# ms5839_without_trub.net
KiCad netlist of a schematic drawn in EAGLE
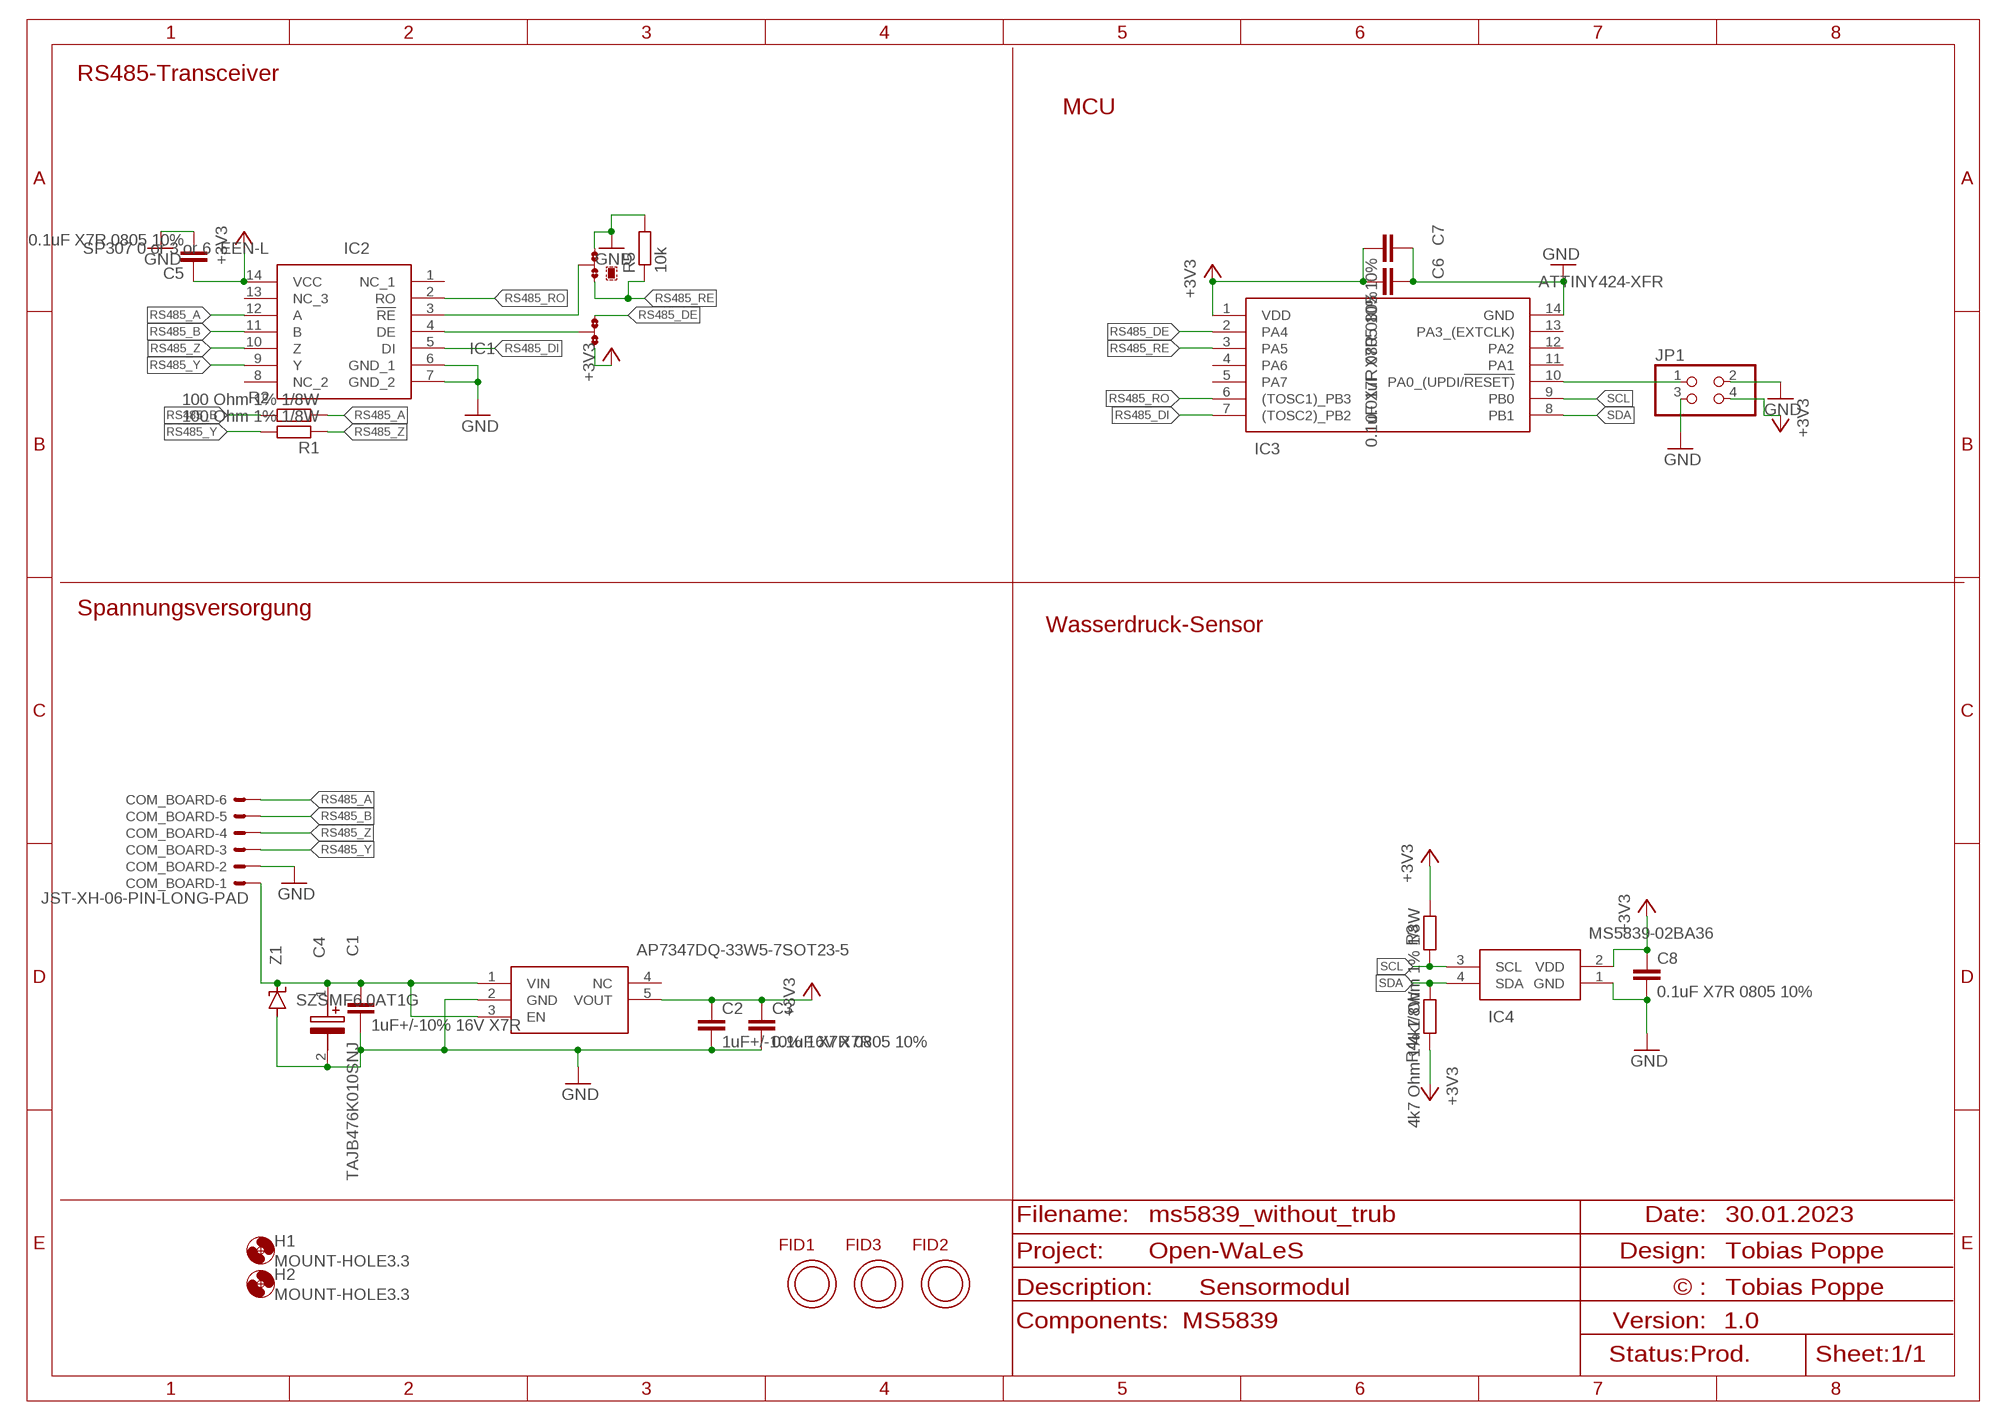
[diagram p0: schematic, sheet 1]

(export (version "E")
  (design (tool "Eeschema 10.0.6"))
  (components
    (comp (ref "C1")
      (value "1uF+/-10% 16V X7R")
      (footprint "eagle-import:C0805")
      (libsource (lib "eagle-import") (part "C-EUC0805"))
    )
    (comp (ref "C2")
      (value "1uF+/-10% 16V X7R")
      (footprint "eagle-import:C0805")
      (libsource (lib "eagle-import") (part "C-EUC0805"))
    )
    (comp (ref "C3")
      (value "0.1uF X7R 0805 10%")
      (footprint "eagle-import:C0805")
      (libsource (lib "eagle-import") (part "C-EUC0805"))
    )
    (comp (ref "C4")
      (value "TAJB476K010SNJ")
      (footprint "eagle-import:CAPPM3528X210N")
      (fields (field (name "MOUSER_PART_NUMBER") "581-TAJB476K010SNJ"))
      (libsource (lib "eagle-import") (part "TAJB476K010SNJ"))
    )
    (comp (ref "C5")
      (value "0.1uF X7R 0805 10%")
      (footprint "eagle-import:C0805")
      (libsource (lib "eagle-import") (part "C-EUC0805"))
    )
    (comp (ref "C6")
      (value "0.1uF X7R 0805 10%")
      (footprint "eagle-import:C0805")
      (libsource (lib "eagle-import") (part "C-EUC0805"))
    )
    (comp (ref "C7")
      (value "0.01uF X7R 0805 10%")
      (footprint "eagle-import:C0805")
      (libsource (lib "eagle-import") (part "C-EUC0805"))
    )
    (comp (ref "C8")
      (value "0.1uF X7R 0805 10%")
      (footprint "eagle-import:C0805")
      (libsource (lib "eagle-import") (part "C-EUC0805"))
    )
    (comp (ref "COM_BOARD")
      (value "JST-XH-06-PIN-LONG-PAD")
      (footprint "eagle-import:JST-XH-06-PACKAGE-LONG-PAD")
      (libsource (lib "eagle-import") (part "JST-XH-06-PIN-LONG-PAD"))
    )
    (comp (ref "FID1")
      (value "OPEN-PNP-FIDUCIAL")
      (footprint "eagle-import:OPEN-PNP-FIDUCIAL")
      (libsource (lib "eagle-import") (part "OPEN-PNP-FIDUCIAL"))
    )
    (comp (ref "FID2")
      (value "OPEN-PNP-FIDUCIAL")
      (footprint "eagle-import:OPEN-PNP-FIDUCIAL")
      (libsource (lib "eagle-import") (part "OPEN-PNP-FIDUCIAL"))
    )
    (comp (ref "FID3")
      (value "OPEN-PNP-FIDUCIAL")
      (footprint "eagle-import:OPEN-PNP-FIDUCIAL")
      (libsource (lib "eagle-import") (part "OPEN-PNP-FIDUCIAL"))
    )
    (comp (ref "H1")
      (value "MOUNT-HOLE3.3")
      (footprint "eagle-import:3,3")
      (libsource (lib "eagle-import") (part "MOUNT-HOLE3.3"))
    )
    (comp (ref "H2")
      (value "MOUNT-HOLE3.3")
      (footprint "eagle-import:3,3")
      (libsource (lib "eagle-import") (part "MOUNT-HOLE3.3"))
    )
    (comp (ref "IC1")
      (value "AP7347DQ-33W5-7SOT23-5")
      (footprint "eagle-import:SOT95P240X110-5N")
      (libsource (lib "eagle-import") (part "AP7347DQ-33W5-7SOT23-5"))
    )
    (comp (ref "IC2")
      (value "SP307 0 or 3 or 6 EEN-L")
      (footprint "eagle-import:SOIC127P600X175-14N")
      (fields
        (field (name "MANUFACTURER_PART_NUMBER") "SP3076EEN-L")
        (field (name "MOUSER_PART_NUMBER") "701-SP3076EEN-L")
      )
      (libsource (lib "eagle-import") (part "SP3076EEN-L"))
    )
    (comp (ref "IC3")
      (value "ATTINY424-XFR")
      (footprint "eagle-import:SOP65P640X120-14N")
      (fields (field (name "MOUSER_PART_NUMBER") "579-ATTINY424-XFR"))
      (libsource (lib "eagle-import") (part "ATTINY424-XFR"))
    )
    (comp (ref "IC4")
      (value "MS5839-02BA36")
      (footprint "eagle-import:MS583902BA36")
      (fields (field (name "MOUSER_PART_NUMBER") "824-MS5839-02BA36"))
      (libsource (lib "eagle-import") (part "MS5839-02BA36"))
    )
    (comp (ref "JMP1")
      (value "0R-JUMPA")
      (footprint "eagle-import:A0R-JMP")
      (libsource (lib "eagle-import") (part "0R-JUMPA"))
    )
    (comp (ref "JMP2")
      (value "0R-JUMPA")
      (footprint "eagle-import:A0R-JMP")
      (libsource (lib "eagle-import") (part "0R-JUMPA"))
    )
    (comp (ref "JP1")
      (value "PINHD-2X2")
      (footprint "eagle-import:2X02")
      (libsource (lib "eagle-import") (part "PINHD-2X2"))
    )
    (comp (ref "R1")
      (value "100 Ohm 1% 1/8W")
      (footprint "eagle-import:R0805")
      (libsource (lib "eagle-import") (part "R-EU_R0805"))
    )
    (comp (ref "R2")
      (value "100 Ohm 1% 1/8W")
      (footprint "eagle-import:R0805")
      (libsource (lib "eagle-import") (part "R-EU_R0805"))
    )
    (comp (ref "R3")
      (value "4k7 Ohm 1% 1/8W")
      (footprint "eagle-import:R0805")
      (libsource (lib "eagle-import") (part "R-EU_R0805"))
    )
    (comp (ref "R4")
      (value "4k7 Ohm 1% 1/8W")
      (footprint "eagle-import:R0805")
      (libsource (lib "eagle-import") (part "R-EU_R0805"))
    )
    (comp (ref "R5")
      (value "10k")
      (footprint "eagle-import:M0805")
      (libsource (lib "eagle-import") (part "R-EU_M0805"))
    )
    (comp (ref "Z1")
      (value "SZSMF6.0AT1G")
      (footprint "eagle-import:SOD123")
      (libsource (lib "eagle-import") (part "SZSMF_XX"))
    )
  )
  (nets
    (net (code "1") (name "+3V3") (class "Default")
      (node (ref "C2") (pin "1") (pinfunction "1_1") (pintype "passive"))
      (node (ref "C3") (pin "1") (pinfunction "1_1") (pintype "passive"))
      (node (ref "C5") (pin "1") (pinfunction "1_1") (pintype "passive"))
      (node (ref "C6") (pin "2") (pinfunction "2_2") (pintype "passive"))
      (node (ref "C7") (pin "2") (pinfunction "2_2") (pintype "passive"))
      (node (ref "C8") (pin "1") (pinfunction "1_1") (pintype "passive"))
      (node (ref "IC1") (pin "5") (pinfunction "VOUT_5") (pintype "bidirectional"))
      (node (ref "IC2") (pin "14") (pinfunction "VCC_14") (pintype "bidirectional"))
      (node (ref "IC3") (pin "1") (pinfunction "VDD_1") (pintype "bidirectional"))
      (node (ref "IC4") (pin "2") (pinfunction "VDD_2") (pintype "bidirectional"))
      (node (ref "JMP1") (pin "1") (pinfunction "1_1") (pintype "passive"))
      (node (ref "JP1") (pin "4") (pinfunction "4_4") (pintype "passive"))
      (node (ref "R3") (pin "1") (pinfunction "1_1") (pintype "passive"))
      (node (ref "R4") (pin "2") (pinfunction "2_2") (pintype "passive"))
    )
    (net (code "2") (name "GND") (class "Default")
      (node (ref "C1") (pin "2") (pinfunction "2_2") (pintype "passive"))
      (node (ref "C2") (pin "2") (pinfunction "2_2") (pintype "passive"))
      (node (ref "C3") (pin "2") (pinfunction "2_2") (pintype "passive"))
      (node (ref "C4") (pin "2") (pinfunction "-_2") (pintype "bidirectional"))
      (node (ref "C5") (pin "2") (pinfunction "2_2") (pintype "passive"))
      (node (ref "C6") (pin "1") (pinfunction "1_1") (pintype "passive"))
      (node (ref "C7") (pin "1") (pinfunction "1_1") (pintype "passive"))
      (node (ref "C8") (pin "2") (pinfunction "2_2") (pintype "passive"))
      (node (ref "COM_BOARD") (pin "2") (pinfunction "S_2") (pintype "passive"))
      (node (ref "IC1") (pin "2") (pinfunction "GND_2") (pintype "bidirectional"))
      (node (ref "IC2") (pin "6") (pinfunction "GND_1_6") (pintype "bidirectional"))
      (node (ref "IC2") (pin "7") (pinfunction "GND_2_7") (pintype "bidirectional"))
      (node (ref "IC3") (pin "14") (pinfunction "GND_14") (pintype "bidirectional"))
      (node (ref "IC4") (pin "1") (pinfunction "GND_1") (pintype "bidirectional"))
      (node (ref "JMP2") (pin "3") (pinfunction "3_3") (pintype "passive"))
      (node (ref "JP1") (pin "2") (pinfunction "2_2") (pintype "passive"))
      (node (ref "JP1") (pin "3") (pinfunction "3_3") (pintype "passive"))
      (node (ref "R5") (pin "2") (pinfunction "2_2") (pintype "passive"))
      (node (ref "Z1") (pin "A") (pinfunction "A_A") (pintype "passive"))
    )
    (net (code "3") (name "Net-(C4-+)") (class "Default")
      (node (ref "C1") (pin "1") (pinfunction "1_1") (pintype "passive"))
      (node (ref "C4") (pin "1") (pinfunction "+_1") (pintype "bidirectional"))
      (node (ref "COM_BOARD") (pin "1") (pinfunction "S_1") (pintype "passive"))
      (node (ref "IC1") (pin "1") (pinfunction "VIN_1") (pintype "bidirectional"))
      (node (ref "IC1") (pin "3") (pinfunction "EN_3") (pintype "bidirectional"))
      (node (ref "Z1") (pin "C") (pinfunction "C_C") (pintype "passive"))
    )
    (net (code "4") (name "Net-(IC2-DE)") (class "Default")
      (node (ref "IC2") (pin "4") (pinfunction "DE_4") (pintype "bidirectional"))
      (node (ref "JMP1") (pin "2") (pinfunction "2_2") (pintype "passive"))
    )
    (net (code "5") (name "Net-(IC2-~{RE})") (class "Default")
      (node (ref "IC2") (pin "3") (pinfunction "~{RE}_3") (pintype "bidirectional"))
      (node (ref "JMP2") (pin "2") (pinfunction "2_2") (pintype "passive"))
    )
    (net (code "6") (name "Net-(IC3-PA0_(UPDI{slash}~{RESET}))") (class "Default")
      (node (ref "IC3") (pin "10") (pinfunction "PA0_(UPDI/~{RESET})_10") (pintype "bidirectional"))
      (node (ref "JP1") (pin "1") (pinfunction "1_1") (pintype "passive"))
    )
    (net (code "7") (name "RS485_A") (class "Default")
      (node (ref "COM_BOARD") (pin "6") (pinfunction "S_6") (pintype "passive"))
      (node (ref "IC2") (pin "12") (pinfunction "A_12") (pintype "bidirectional"))
      (node (ref "R2") (pin "1") (pinfunction "1_1") (pintype "passive"))
    )
    (net (code "8") (name "RS485_B") (class "Default")
      (node (ref "COM_BOARD") (pin "5") (pinfunction "S_5") (pintype "passive"))
      (node (ref "IC2") (pin "11") (pinfunction "B_11") (pintype "bidirectional"))
      (node (ref "R2") (pin "2") (pinfunction "2_2") (pintype "passive"))
    )
    (net (code "9") (name "RS485_DE") (class "Default")
      (node (ref "IC3") (pin "2") (pinfunction "PA4_2") (pintype "bidirectional"))
      (node (ref "JMP1") (pin "3") (pinfunction "3_3") (pintype "passive"))
    )
    (net (code "10") (name "RS485_DI") (class "Default")
      (node (ref "IC2") (pin "5") (pinfunction "DI_5") (pintype "bidirectional"))
      (node (ref "IC3") (pin "7") (pinfunction "(TOSC2)_PB2_7") (pintype "bidirectional"))
    )
    (net (code "11") (name "RS485_RE") (class "Default")
      (node (ref "IC3") (pin "3") (pinfunction "PA5_3") (pintype "bidirectional"))
      (node (ref "JMP2") (pin "1") (pinfunction "1_1") (pintype "passive"))
      (node (ref "R5") (pin "1") (pinfunction "1_1") (pintype "passive"))
    )
    (net (code "12") (name "RS485_RO") (class "Default")
      (node (ref "IC2") (pin "2") (pinfunction "RO_2") (pintype "bidirectional"))
      (node (ref "IC3") (pin "6") (pinfunction "(TOSC1)_PB3_6") (pintype "bidirectional"))
    )
    (net (code "13") (name "RS485_Y") (class "Default")
      (node (ref "COM_BOARD") (pin "3") (pinfunction "S_3") (pintype "passive"))
      (node (ref "IC2") (pin "9") (pinfunction "Y_9") (pintype "bidirectional"))
      (node (ref "R1") (pin "2") (pinfunction "2_2") (pintype "passive"))
    )
    (net (code "14") (name "RS485_Z") (class "Default")
      (node (ref "COM_BOARD") (pin "4") (pinfunction "S_4") (pintype "passive"))
      (node (ref "IC2") (pin "10") (pinfunction "Z_10") (pintype "bidirectional"))
      (node (ref "R1") (pin "1") (pinfunction "1_1") (pintype "passive"))
    )
    (net (code "15") (name "SCL") (class "Default")
      (node (ref "IC3") (pin "9") (pinfunction "PB0_9") (pintype "bidirectional"))
      (node (ref "IC4") (pin "3") (pinfunction "SCL_3") (pintype "bidirectional"))
      (node (ref "R3") (pin "2") (pinfunction "2_2") (pintype "passive"))
    )
    (net (code "16") (name "SDA") (class "Default")
      (node (ref "IC3") (pin "8") (pinfunction "PB1_8") (pintype "bidirectional"))
      (node (ref "IC4") (pin "4") (pinfunction "SDA_4") (pintype "bidirectional"))
      (node (ref "R4") (pin "1") (pinfunction "1_1") (pintype "passive"))
    )
    (net (code "17") (name "unconnected-(IC1-NC-Pad4)") (class "Default")
      (node (ref "IC1") (pin "4") (pinfunction "NC_4") (pintype "no_connect"))
    )
    (net (code "18") (name "unconnected-(IC2-NC_1-Pad1)") (class "Default")
      (node (ref "IC2") (pin "1") (pinfunction "NC_1_1") (pintype "bidirectional"))
    )
    (net (code "19") (name "unconnected-(IC2-NC_2-Pad8)") (class "Default")
      (node (ref "IC2") (pin "8") (pinfunction "NC_2_8") (pintype "bidirectional"))
    )
    (net (code "20") (name "unconnected-(IC2-NC_3-Pad13)") (class "Default")
      (node (ref "IC2") (pin "13") (pinfunction "NC_3_13") (pintype "bidirectional"))
    )
    (net (code "21") (name "unconnected-(IC3-PA1-Pad11)") (class "Default")
      (node (ref "IC3") (pin "11") (pinfunction "PA1_11") (pintype "bidirectional"))
    )
    (net (code "22") (name "unconnected-(IC3-PA2-Pad12)") (class "Default")
      (node (ref "IC3") (pin "12") (pinfunction "PA2_12") (pintype "bidirectional"))
    )
    (net (code "23") (name "unconnected-(IC3-PA3_(EXTCLK)-Pad13)") (class "Default")
      (node (ref "IC3") (pin "13") (pinfunction "PA3_(EXTCLK)_13") (pintype "bidirectional"))
    )
    (net (code "24") (name "unconnected-(IC3-PA6-Pad4)") (class "Default")
      (node (ref "IC3") (pin "4") (pinfunction "PA6_4") (pintype "bidirectional"))
    )
    (net (code "25") (name "unconnected-(IC3-PA7-Pad5)") (class "Default")
      (node (ref "IC3") (pin "5") (pinfunction "PA7_5") (pintype "bidirectional"))
    )
  )
)
